# design.net
KiCad netlist of a schematic drawn in Altium Designer
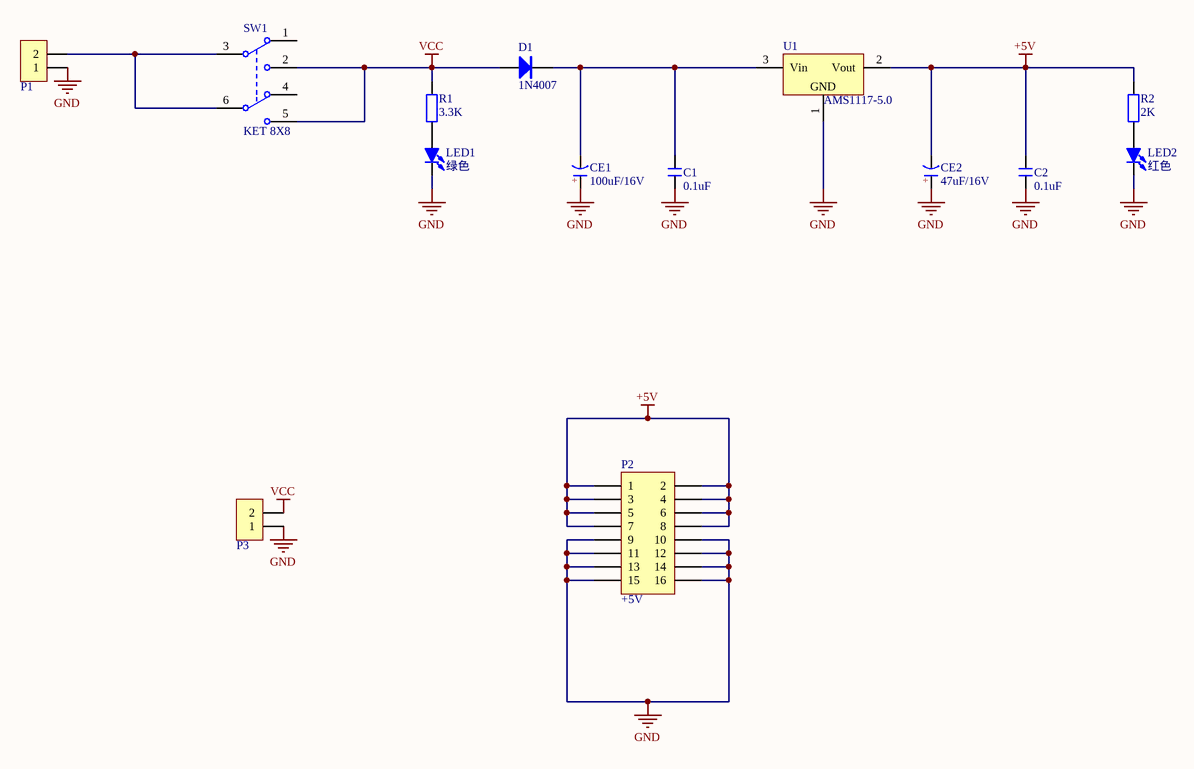
[diagram p0: 电源.SchDoc]

(export (version "E")
  (design (tool "Eeschema 10.0.6"))
  (components
    (comp (ref "C1")
      (value "0.1uF")
      (footprint "C 0805_L")
      (description "贴片电容")
      (libsource (lib "0.1 - 电阻-电容-电感") (part "C"))
    )
    (comp (ref "C2")
      (value "0.1uF")
      (footprint "C 0805_L")
      (description "贴片电容")
      (libsource (lib "0.1 - 电阻-电容-电感") (part "C"))
    )
    (comp (ref "CE1")
      (value "100uF/16V")
      (footprint "CAP 2.5*6.3*11.2 - BK")
      (description "直插电解电容")
      (libsource (lib "0.1 - 电阻-电容-电感") (part "CE"))
    )
    (comp (ref "CE2")
      (value "47uF/16V")
      (footprint "CAP 2.0*5*11 - BK")
      (description "直插电解电容")
      (libsource (lib "0.1 - 电阻-电容-电感") (part "CE"))
    )
    (comp (ref "D1")
      (value "1N4007")
      (footprint "SOD-123")
      (description "整流二极管")
      (libsource (lib "0.2 - 二极管-整流桥") (part "1N4007"))
    )
    (comp (ref "LED1")
      (value "绿色")
      (footprint "LED 0805G")
      (description "贴片LED")
      (fields (field (name "版权归属") "封装库来自淘宝 ID：黄晶宝石"))
      (libsource (lib "0.3 - LED发光二极管") (part "LED-SMD"))
    )
    (comp (ref "LED2")
      (value "红色")
      (footprint "LED 0805R")
      (description "贴片LED")
      (fields (field (name "版权归属") "封装库来自淘宝 ID：黄晶宝石"))
      (libsource (lib "0.3 - LED发光二极管") (part "LED-SMD"))
    )
    (comp (ref "P1")
      (value "HDR-1X2")
      (footprint "KF301-5.0-2P")
      (description "2P接插件")
      (fields (field (name "版权归属") "封装库来自淘宝 ID：黄晶宝石"))
      (libsource (lib "6.0 - 接插件-脚距5.0") (part "Header 2"))
    )
    (comp (ref "P2")
      (value "+5V")
      (footprint "HDR2X8")
      (description "Header, 8-Pin, Dual row")
      (fields (field (name "PUBLISHER") "Altium Limited"))
      (libsource (lib "Miscellaneous Connectors") (part "Header 8X2"))
    )
    (comp (ref "P3")
      (value "HDR-1X2")
      (footprint "KF301-5.0-2P")
      (description "2P接插件")
      (fields (field (name "版权归属") "封装库来自淘宝 ID：黄晶宝石"))
      (libsource (lib "6.0 - 接插件-脚距5.0") (part "Header 2"))
    )
    (comp (ref "R1")
      (value "3.3K")
      (footprint "R 0805_L")
      (description "贴片电阻")
      (fields (field (name "版权归属") "来自淘宝 ID：黄晶宝石"))
      (libsource (lib "0.1 - 电阻-电容-电感") (part "R"))
    )
    (comp (ref "R2")
      (value "2K")
      (footprint "R 0805_L")
      (description "贴片电阻")
      (fields (field (name "版权归属") "来自淘宝 ID：黄晶宝石"))
      (libsource (lib "0.1 - 电阻-电容-电感") (part "R"))
    )
    (comp (ref "SW1")
      (value "KET 8X8")
      (footprint "KFT DIP-8X8")
      (description "8*8自锁开关")
      (fields (field (name "版权归属") "封装库来自淘宝 ID：黄晶宝石"))
      (libsource (lib "0.7 - 常用按键-开关") (part "KET 8X8"))
    )
    (comp (ref "U1")
      (value "AMS1117-5.0")
      (footprint "SOT223_L")
      (description "三端稳压芯片")
      (libsource (lib "1.1 - 电源类芯片") (part "AMS1117"))
    )
  )
  (nets
    (net (code "1") (name "+5V") (class "Default")
      (node (ref "C2") (pin "2") (pinfunction "2_2") (pintype "passive"))
      (node (ref "CE2") (pin "2") (pinfunction "K_2") (pintype "passive"))
      (node (ref "P2") (pin "1") (pinfunction "1_1") (pintype "passive"))
      (node (ref "P2") (pin "2") (pinfunction "2_2") (pintype "passive"))
      (node (ref "P2") (pin "3") (pinfunction "3_3") (pintype "passive"))
      (node (ref "P2") (pin "4") (pinfunction "4_4") (pintype "passive"))
      (node (ref "P2") (pin "5") (pinfunction "5_5") (pintype "passive"))
      (node (ref "P2") (pin "6") (pinfunction "6_6") (pintype "passive"))
      (node (ref "P2") (pin "7") (pinfunction "7_7") (pintype "passive"))
      (node (ref "P2") (pin "8") (pinfunction "8_8") (pintype "passive"))
      (node (ref "R2") (pin "2") (pinfunction "2_2") (pintype "passive"))
      (node (ref "U1") (pin "2") (pinfunction "Vout_2") (pintype "passive"))
    )
    (net (code "2") (name "GND") (class "Default")
      (node (ref "C1") (pin "1") (pinfunction "1_1") (pintype "passive"))
      (node (ref "C2") (pin "1") (pinfunction "1_1") (pintype "passive"))
      (node (ref "CE1") (pin "1") (pinfunction "A_1") (pintype "passive"))
      (node (ref "CE2") (pin "1") (pinfunction "A_1") (pintype "passive"))
      (node (ref "LED1") (pin "2") (pinfunction "K_2") (pintype "passive"))
      (node (ref "LED2") (pin "2") (pinfunction "K_2") (pintype "passive"))
      (node (ref "P1") (pin "1") (pinfunction "1_1") (pintype "passive"))
      (node (ref "P2") (pin "10") (pinfunction "10_10") (pintype "passive"))
      (node (ref "P2") (pin "11") (pinfunction "11_11") (pintype "passive"))
      (node (ref "P2") (pin "12") (pinfunction "12_12") (pintype "passive"))
      (node (ref "P2") (pin "13") (pinfunction "13_13") (pintype "passive"))
      (node (ref "P2") (pin "14") (pinfunction "14_14") (pintype "passive"))
      (node (ref "P2") (pin "15") (pinfunction "15_15") (pintype "passive"))
      (node (ref "P2") (pin "16") (pinfunction "16_16") (pintype "passive"))
      (node (ref "P2") (pin "9") (pinfunction "9_9") (pintype "passive"))
      (node (ref "P3") (pin "1") (pinfunction "1_1") (pintype "passive"))
      (node (ref "U1") (pin "1") (pinfunction "GND_1") (pintype "passive"))
    )
    (net (code "3") (name "Net-(CE1-K)") (class "Default")
      (node (ref "C1") (pin "2") (pinfunction "2_2") (pintype "passive"))
      (node (ref "CE1") (pin "2") (pinfunction "K_2") (pintype "passive"))
      (node (ref "D1") (pin "2") (pinfunction "K_2") (pintype "passive"))
      (node (ref "U1") (pin "3") (pinfunction "Vin_3") (pintype "passive"))
    )
    (net (code "4") (name "Net-(LED1-A)") (class "Default")
      (node (ref "LED1") (pin "1") (pinfunction "A_1") (pintype "passive"))
      (node (ref "R1") (pin "1") (pinfunction "1_1") (pintype "passive"))
    )
    (net (code "5") (name "Net-(LED2-A)") (class "Default")
      (node (ref "LED2") (pin "1") (pinfunction "A_1") (pintype "passive"))
      (node (ref "R2") (pin "1") (pinfunction "1_1") (pintype "passive"))
    )
    (net (code "6") (name "Net-(SW1-NC2)") (class "Default")
      (node (ref "P1") (pin "2") (pinfunction "2_2") (pintype "passive"))
      (node (ref "SW1") (pin "3") (pinfunction "NO1_3") (pintype "passive"))
      (node (ref "SW1") (pin "6") (pinfunction "NC2_6") (pintype "passive"))
    )
    (net (code "7") (name "VCC") (class "Default")
      (node (ref "D1") (pin "1") (pinfunction "A_1") (pintype "passive"))
      (node (ref "P3") (pin "2") (pinfunction "2_2") (pintype "passive"))
      (node (ref "R1") (pin "2") (pinfunction "2_2") (pintype "passive"))
      (node (ref "SW1") (pin "2") (pinfunction "COM2_2") (pintype "passive"))
      (node (ref "SW1") (pin "5") (pinfunction "COM2_5") (pintype "passive"))
    )
    (net (code "8") (name "unconnected-(SW1-NC1-Pad1)") (class "Default")
      (node (ref "SW1") (pin "1") (pinfunction "NC1_1") (pintype "passive"))
    )
    (net (code "9") (name "unconnected-(SW1-NO2-Pad4)") (class "Default")
      (node (ref "SW1") (pin "4") (pinfunction "NO2_4") (pintype "passive"))
    )
  )
)
